# adc_microboard.net
KiCad netlist of a schematic drawn in EAGLE
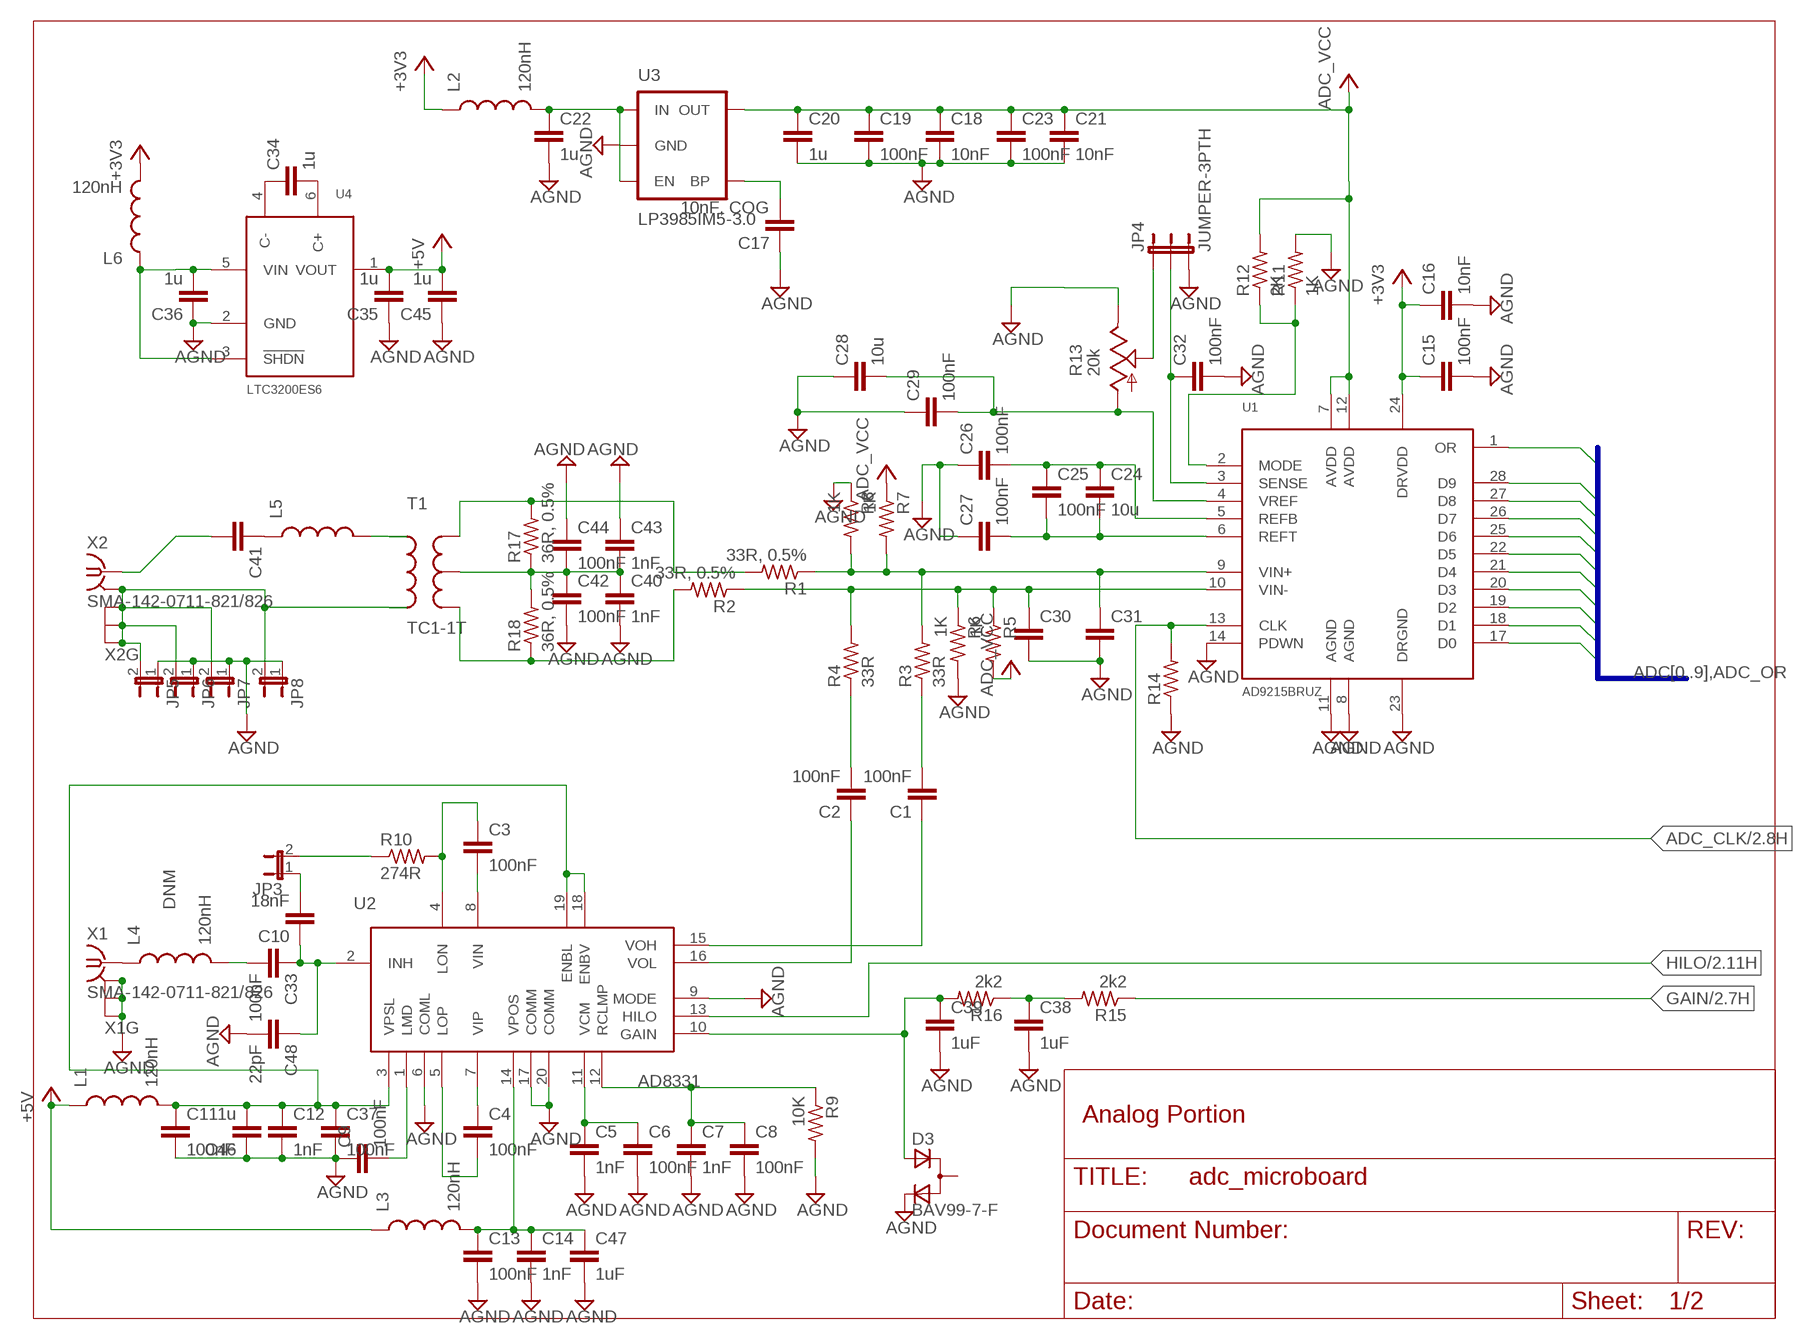
[diagram p0: schematic, sheet 1]
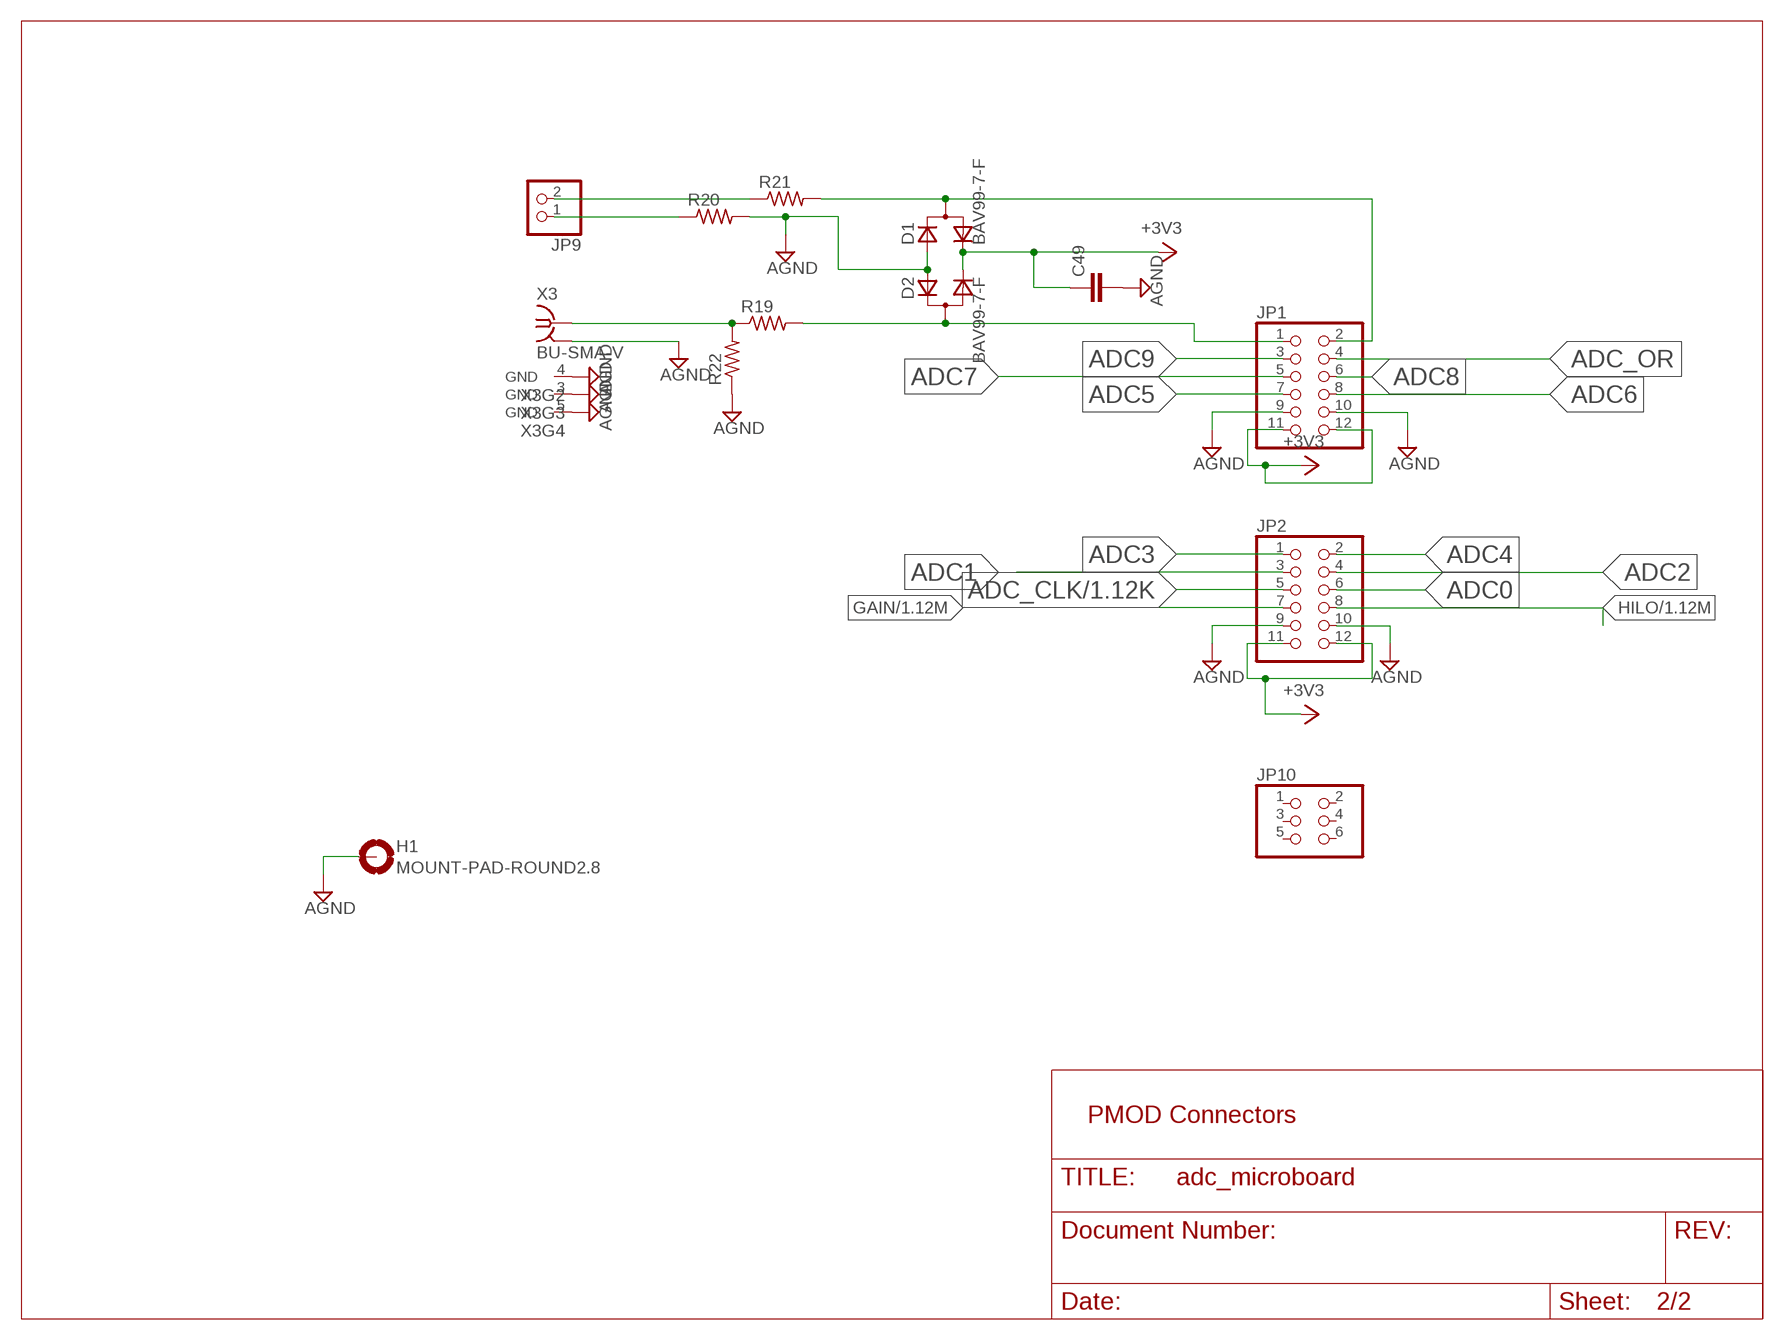
[diagram p1: schematic, sheet 2]

(export (version "E")
  (design (tool "Eeschema 10.0.6"))
  (components
    (comp (ref "C49")
      (value "C-EUC0603")
      (footprint "eagle-import:C0603")
      (libsource (lib "eagle-import") (part "C-EUC0603"))
    )
    (comp (ref "D1")
      (value "BAV99-7-F")
      (footprint "eagle-import:SOT-23")
      (libsource (lib "eagle-import") (part "D_ACACSOT23"))
    )
    (comp (ref "D2")
      (value "BAV99-7-F")
      (footprint "eagle-import:SOT-23")
      (libsource (lib "eagle-import") (part "D_ACACSOT23"))
    )
    (comp (ref "H1")
      (value "MOUNT-PAD-ROUND2.8")
      (footprint "eagle-import:2,8-PAD")
      (libsource (lib "eagle-import") (part "MOUNT-PAD-ROUND2.8"))
    )
    (comp (ref "JP1")
      (value "PINHD-2X6")
      (footprint "eagle-import:2X06")
      (libsource (lib "eagle-import") (part "PINHD-2X6"))
    )
    (comp (ref "JP2")
      (value "PINHD-2X6")
      (footprint "eagle-import:2X06")
      (libsource (lib "eagle-import") (part "PINHD-2X6"))
    )
    (comp (ref "JP9")
      (value "PINHD-1X2/90")
      (footprint "eagle-import:1X02_90")
      (libsource (lib "eagle-import") (part "PINHD-1X2/90"))
    )
    (comp (ref "JP10")
      (value "PINHD-2X3")
      (footprint "eagle-import:2X03")
      (libsource (lib "eagle-import") (part "PINHD-2X3"))
    )
    (comp (ref "R19")
      (value "R-US_R0805")
      (footprint "eagle-import:R0805")
      (libsource (lib "eagle-import") (part "R-US_R0805"))
    )
    (comp (ref "R20")
      (value "R-US_R0603")
      (footprint "eagle-import:R0603")
      (libsource (lib "eagle-import") (part "R-US_R0603"))
    )
    (comp (ref "R21")
      (value "R-US_R0603")
      (footprint "eagle-import:R0603")
      (libsource (lib "eagle-import") (part "R-US_R0603"))
    )
    (comp (ref "R22")
      (value "R-US_R0603")
      (footprint "eagle-import:R0603")
      (libsource (lib "eagle-import") (part "R-US_R0603"))
    )
    (comp (ref "X3")
      (value "BU-SMA-V")
      (footprint "eagle-import:BU-SMA-V")
      (libsource (lib "eagle-import") (part "BU-SMA-V"))
    )
    (comp (ref "C1")
      (value "100nF")
      (footprint "eagle-import:C0603K")
      (libsource (lib "eagle-import") (part "rcl_C-EUC0603K"))
    )
    (comp (ref "C2")
      (value "100nF")
      (footprint "eagle-import:C0603K")
      (libsource (lib "eagle-import") (part "rcl_C-EUC0603K"))
    )
    (comp (ref "C3")
      (value "100nF")
      (footprint "eagle-import:C0402")
      (libsource (lib "eagle-import") (part "rcl_C-EUC0402"))
    )
    (comp (ref "C4")
      (value "100nF")
      (footprint "eagle-import:C0402")
      (libsource (lib "eagle-import") (part "rcl_C-EUC0402"))
    )
    (comp (ref "C5")
      (value "1nF")
      (footprint "eagle-import:C0402")
      (fields (field (name "PART#") "C1005X7R1E102K"))
      (libsource (lib "eagle-import") (part "rcl_C-EUC0402"))
    )
    (comp (ref "C6")
      (value "100nF")
      (footprint "eagle-import:C0402")
      (fields (field (name "PART#") "GRM155R61A104KA01D"))
      (libsource (lib "eagle-import") (part "rcl_C-EUC0402"))
    )
    (comp (ref "C7")
      (value "1nF")
      (footprint "eagle-import:C0402")
      (fields (field (name "PART#") "C1005X7R1E102K"))
      (libsource (lib "eagle-import") (part "rcl_C-EUC0402"))
    )
    (comp (ref "C8")
      (value "100nF")
      (footprint "eagle-import:C0402")
      (fields (field (name "PART#") "GRM155R61A104KA01D"))
      (libsource (lib "eagle-import") (part "rcl_C-EUC0402"))
    )
    (comp (ref "C9")
      (value "100nF")
      (footprint "eagle-import:C0402")
      (fields (field (name "PART#") "GRM155R61A104KA01D"))
      (libsource (lib "eagle-import") (part "rcl_C-EUC0402"))
    )
    (comp (ref "C10")
      (value "18nF")
      (footprint "eagle-import:C0603")
      (libsource (lib "eagle-import") (part "rcl_C-EUC0603"))
    )
    (comp (ref "C11")
      (value "100nF")
      (footprint "eagle-import:C0402")
      (fields (field (name "PART#") "GRM155R61A104KA01D"))
      (libsource (lib "eagle-import") (part "rcl_C-EUC0402"))
    )
    (comp (ref "C12")
      (value "1nF")
      (footprint "eagle-import:C0402")
      (fields (field (name "PART#") "C1005X7R1E102K"))
      (libsource (lib "eagle-import") (part "rcl_C-EUC0402"))
    )
    (comp (ref "C13")
      (value "100nF")
      (footprint "eagle-import:C0402")
      (fields (field (name "PART#") "GRM155R61A104KA01D"))
      (libsource (lib "eagle-import") (part "rcl_C-EUC0402"))
    )
    (comp (ref "C14")
      (value "1nF")
      (footprint "eagle-import:C0402")
      (fields (field (name "PART#") "C1005X7R1E102K"))
      (libsource (lib "eagle-import") (part "rcl_C-EUC0402"))
    )
    (comp (ref "C15")
      (value "100nF")
      (footprint "eagle-import:C0402")
      (fields (field (name "PART#") "GRM155R61A104KA01D"))
      (libsource (lib "eagle-import") (part "rcl_C-EUC0402"))
    )
    (comp (ref "C16")
      (value "10nF")
      (footprint "eagle-import:C0402")
      (libsource (lib "eagle-import") (part "rcl_C-EUC0402"))
    )
    (comp (ref "C17")
      (value "10nF, COG")
      (footprint "eagle-import:C0402")
      (libsource (lib "eagle-import") (part "rcl_C-EUC0402"))
    )
    (comp (ref "C18")
      (value "10nF")
      (footprint "eagle-import:C0402")
      (fields (field (name "PART#") "GRM155R71E103KA01D"))
      (libsource (lib "eagle-import") (part "rcl_C-EUC0402"))
    )
    (comp (ref "C19")
      (value "100nF")
      (footprint "eagle-import:C0402")
      (fields (field (name "PART#") "GRM155R61A104KA01D"))
      (libsource (lib "eagle-import") (part "rcl_C-EUC0402"))
    )
    (comp (ref "C20")
      (value "1u")
      (footprint "eagle-import:C0603")
      (fields (field (name "PART#") "GRM188R61A105KA61D"))
      (libsource (lib "eagle-import") (part "rcl_C-EUC0603"))
    )
    (comp (ref "C21")
      (value "10nF")
      (footprint "eagle-import:C0402")
      (fields (field (name "PART#") "GRM155R71E103KA01D"))
      (libsource (lib "eagle-import") (part "rcl_C-EUC0402"))
    )
    (comp (ref "C22")
      (value "1u")
      (footprint "eagle-import:C0603")
      (fields (field (name "PART#") "GRM188R61A105KA61D"))
      (libsource (lib "eagle-import") (part "rcl_C-EUC0603"))
    )
    (comp (ref "C23")
      (value "100nF")
      (footprint "eagle-import:C0402")
      (fields (field (name "PART#") "GRM155R61A104KA01D"))
      (libsource (lib "eagle-import") (part "rcl_C-EUC0402"))
    )
    (comp (ref "C24")
      (value "10u")
      (footprint "eagle-import:C0603")
      (libsource (lib "eagle-import") (part "rcl_C-EUC0603"))
    )
    (comp (ref "C25")
      (value "100nF")
      (footprint "eagle-import:C0402")
      (fields (field (name "PART#") "GRM155R61A104KA01D"))
      (libsource (lib "eagle-import") (part "rcl_C-EUC0402"))
    )
    (comp (ref "C26")
      (value "100nF")
      (footprint "eagle-import:C0402")
      (fields (field (name "PART#") "GRM155R61A104KA01D"))
      (libsource (lib "eagle-import") (part "rcl_C-EUC0402"))
    )
    (comp (ref "C27")
      (value "100nF")
      (footprint "eagle-import:C0402")
      (fields (field (name "PART#") "GRM155R61A104KA01D"))
      (libsource (lib "eagle-import") (part "rcl_C-EUC0402"))
    )
    (comp (ref "C28")
      (value "10u")
      (footprint "eagle-import:C0603")
      (libsource (lib "eagle-import") (part "rcl_C-EUC0603"))
    )
    (comp (ref "C29")
      (value "100nF")
      (footprint "eagle-import:C0402")
      (fields (field (name "PART#") "GRM155R61A104KA01D"))
      (libsource (lib "eagle-import") (part "rcl_C-EUC0402"))
    )
    (comp (ref "C30")
      (value "C-EUC0402")
      (footprint "eagle-import:C0402")
      (libsource (lib "eagle-import") (part "rcl_C-EUC0402"))
    )
    (comp (ref "C31")
      (value "C-EUC0402")
      (footprint "eagle-import:C0402")
      (libsource (lib "eagle-import") (part "rcl_C-EUC0402"))
    )
    (comp (ref "C32")
      (value "100nF")
      (footprint "eagle-import:C0402")
      (fields (field (name "PART#") "GRM155R61A104KA01D"))
      (libsource (lib "eagle-import") (part "rcl_C-EUC0402"))
    )
    (comp (ref "C33")
      (value "100nF")
      (footprint "eagle-import:C0603K")
      (libsource (lib "eagle-import") (part "rcl_C-EUC0603K"))
    )
    (comp (ref "C34")
      (value "1u")
      (footprint "eagle-import:C0603")
      (fields (field (name "PART#") "GRM188R61A105KA61D"))
      (libsource (lib "eagle-import") (part "rcl_C-EUC0603"))
    )
    (comp (ref "C35")
      (value "1u")
      (footprint "eagle-import:C0603")
      (fields (field (name "PART#") "GRM188R61A105KA61D"))
      (libsource (lib "eagle-import") (part "rcl_C-EUC0603"))
    )
    (comp (ref "C36")
      (value "1u")
      (footprint "eagle-import:C0603")
      (fields (field (name "PART#") "GRM188R61A105KA61D"))
      (libsource (lib "eagle-import") (part "rcl_C-EUC0603"))
    )
    (comp (ref "C37")
      (value "100nF")
      (footprint "eagle-import:C0402")
      (fields (field (name "PART#") "GRM155R61A104KA01D"))
      (libsource (lib "eagle-import") (part "rcl_C-EUC0402"))
    )
    (comp (ref "C38")
      (value "1uF")
      (footprint "eagle-import:C0603")
      (libsource (lib "eagle-import") (part "rcl_C-EUC0603"))
    )
    (comp (ref "C39")
      (value "1uF")
      (footprint "eagle-import:C0603")
      (libsource (lib "eagle-import") (part "rcl_C-EUC0603"))
    )
    (comp (ref "C40")
      (value "1nF")
      (footprint "eagle-import:C0402")
      (fields (field (name "PART#") "C1005X7R1E102K"))
      (libsource (lib "eagle-import") (part "rcl_C-EUC0402"))
    )
    (comp (ref "C41")
      (value "C-EUC0603K")
      (footprint "eagle-import:C0603K")
      (libsource (lib "eagle-import") (part "rcl_C-EUC0603K"))
    )
    (comp (ref "C42")
      (value "100nF")
      (footprint "eagle-import:C0402")
      (fields (field (name "PART#") "GRM155R61A104KA01D"))
      (libsource (lib "eagle-import") (part "rcl_C-EUC0402"))
    )
    (comp (ref "C43")
      (value "1nF")
      (footprint "eagle-import:C0402")
      (fields (field (name "PART#") "C1005X7R1E102K"))
      (libsource (lib "eagle-import") (part "rcl_C-EUC0402"))
    )
    (comp (ref "C44")
      (value "100nF")
      (footprint "eagle-import:C0402")
      (fields (field (name "PART#") "GRM155R61A104KA01D"))
      (libsource (lib "eagle-import") (part "rcl_C-EUC0402"))
    )
    (comp (ref "C45")
      (value "1u")
      (footprint "eagle-import:C0603")
      (fields (field (name "PART#") "GRM188R61A105KA61D"))
      (libsource (lib "eagle-import") (part "rcl_C-EUC0603"))
    )
    (comp (ref "C46")
      (value "1u")
      (footprint "eagle-import:C0402")
      (fields (field (name "PART#") "GRM188R61A105KA61D"))
      (libsource (lib "eagle-import") (part "rcl_C-EUC0402"))
    )
    (comp (ref "C47")
      (value "1uF")
      (footprint "eagle-import:C0402")
      (fields (field (name "PART#") "C1005X7R1E102K"))
      (libsource (lib "eagle-import") (part "rcl_C-EUC0402"))
    )
    (comp (ref "C48")
      (value "22pF")
      (footprint "eagle-import:C0603")
      (libsource (lib "eagle-import") (part "rcl_C-EUC0603"))
    )
    (comp (ref "D3")
      (value "BAV99-7-F")
      (footprint "eagle-import:SOT-23")
      (libsource (lib "eagle-import") (part "D_ACACSOT23"))
    )
    (comp (ref "JP3")
      (value "JUMPER-2SMD-NC")
      (footprint "eagle-import:SJ_2S")
      (libsource (lib "eagle-import") (part "JUMPER-2SMD-NC"))
    )
    (comp (ref "JP4")
      (value "JUMPER-3PTH")
      (footprint "eagle-import:1X03")
      (libsource (lib "eagle-import") (part "JUMPER-3PTH"))
    )
    (comp (ref "JP5")
      (value "JUMPER-2SMD-NC")
      (footprint "eagle-import:SJ_2S")
      (libsource (lib "eagle-import") (part "JUMPER-2SMD-NC"))
    )
    (comp (ref "JP6")
      (value "JUMPER-2SMD-NC")
      (footprint "eagle-import:SJ_2S")
      (libsource (lib "eagle-import") (part "JUMPER-2SMD-NC"))
    )
    (comp (ref "JP7")
      (value "JUMPER-2SMD-NC")
      (footprint "eagle-import:SJ_2S")
      (libsource (lib "eagle-import") (part "JUMPER-2SMD-NC"))
    )
    (comp (ref "JP8")
      (value "JUMPER-2SMD-NC")
      (footprint "eagle-import:SJ_2S")
      (libsource (lib "eagle-import") (part "JUMPER-2SMD-NC"))
    )
    (comp (ref "L1")
      (value "120nH")
      (footprint "eagle-import:0603")
      (fields (field (name "PART#") "MLF1608DR12M"))
      (libsource (lib "eagle-import") (part "INDUCTOR0603"))
    )
    (comp (ref "L2")
      (value "120nH")
      (footprint "eagle-import:0603")
      (libsource (lib "eagle-import") (part "INDUCTOR0603"))
    )
    (comp (ref "L3")
      (value "120nH")
      (footprint "eagle-import:0603")
      (libsource (lib "eagle-import") (part "INDUCTOR0603"))
    )
    (comp (ref "L4")
      (value "120nH")
      (footprint "eagle-import:0603")
      (libsource (lib "eagle-import") (part "INDUCTOR0603"))
    )
    (comp (ref "L5")
      (value "INDUCTOR0603")
      (footprint "eagle-import:0603")
      (libsource (lib "eagle-import") (part "INDUCTOR0603"))
    )
    (comp (ref "L6")
      (value "120nH")
      (footprint "eagle-import:0603")
      (libsource (lib "eagle-import") (part "INDUCTOR0603"))
    )
    (comp (ref "R1")
      (value "33R, 0.5%")
      (footprint "eagle-import:R0603")
      (libsource (lib "eagle-import") (part "R-US_R0603"))
    )
    (comp (ref "R2")
      (value "33R, 0.5%")
      (footprint "eagle-import:R0603")
      (libsource (lib "eagle-import") (part "R-US_R0603"))
    )
    (comp (ref "R3")
      (value "33R")
      (footprint "eagle-import:R0603")
      (libsource (lib "eagle-import") (part "R-US_R0603"))
    )
    (comp (ref "R4")
      (value "33R")
      (footprint "eagle-import:R0603")
      (libsource (lib "eagle-import") (part "R-US_R0603"))
    )
    (comp (ref "R5")
      (value "1K")
      (footprint "eagle-import:R0402")
      (libsource (lib "eagle-import") (part "R-US_R0402"))
    )
    (comp (ref "R6")
      (value "1K")
      (footprint "eagle-import:R0402")
      (libsource (lib "eagle-import") (part "R-US_R0402"))
    )
    (comp (ref "R7")
      (value "1K")
      (footprint "eagle-import:R0402")
      (libsource (lib "eagle-import") (part "R-US_R0402"))
    )
    (comp (ref "R8")
      (value "1K")
      (footprint "eagle-import:R0402")
      (libsource (lib "eagle-import") (part "R-US_R0402"))
    )
    (comp (ref "R9")
      (value "10K")
      (footprint "eagle-import:R0603")
      (libsource (lib "eagle-import") (part "R-US_R0603"))
    )
    (comp (ref "R10")
      (value "274R")
      (footprint "eagle-import:R0603")
      (libsource (lib "eagle-import") (part "R-US_R0603"))
    )
    (comp (ref "R11")
      (value "1K")
      (footprint "eagle-import:R0402")
      (libsource (lib "eagle-import") (part "R-US_R0402"))
    )
    (comp (ref "R12")
      (value "2K")
      (footprint "eagle-import:R0603")
      (libsource (lib "eagle-import") (part "R-US_R0603"))
    )
    (comp (ref "R13")
      (value "20k")
      (footprint "eagle-import:3361P")
      (fields (field (name "PART#") "3361P-1-203GLF"))
      (libsource (lib "eagle-import") (part "TRIM_US-3361P"))
    )
    (comp (ref "R14")
      (value "R-US_R0603")
      (footprint "eagle-import:R0603")
      (libsource (lib "eagle-import") (part "R-US_R0603"))
    )
    (comp (ref "R15")
      (value "2k2")
      (footprint "eagle-import:R0603")
      (libsource (lib "eagle-import") (part "R-US_R0603"))
    )
    (comp (ref "R16")
      (value "2k2")
      (footprint "eagle-import:R0603")
      (libsource (lib "eagle-import") (part "R-US_R0603"))
    )
    (comp (ref "R17")
      (value "36R, 0.5%")
      (footprint "eagle-import:R0603")
      (libsource (lib "eagle-import") (part "R-US_R0603"))
    )
    (comp (ref "R18")
      (value "36R, 0.5%")
      (footprint "eagle-import:R0603")
      (libsource (lib "eagle-import") (part "R-US_R0603"))
    )
    (comp (ref "T1")
      (value "TC1-1T")
      (footprint "eagle-import:AT224-1A")
      (libsource (lib "eagle-import") (part "TC1-1T"))
    )
    (comp (ref "U1")
      (value "AD9215BRUZ")
      (footprint "eagle-import:TSSOP28")
      (libsource (lib "eagle-import") (part "AD9215BRUZ"))
    )
    (comp (ref "U2")
      (value "AD8331")
      (footprint "eagle-import:QSOP20")
      (fields (field (name "PART#") "AD8331ARQZ"))
      (libsource (lib "eagle-import") (part "AD8331"))
    )
    (comp (ref "U3")
      (value "LP3985IM5-3.0")
      (footprint "eagle-import:SOT23-5")
      (libsource (lib "eagle-import") (part "V_REG_LDOSMD"))
    )
    (comp (ref "U4")
      (value "LTC3200ES6")
      (footprint "eagle-import:SOT23-6L")
      (fields (field (name "PART#") "LTC3200ES6-5#TRMPBF"))
      (libsource (lib "eagle-import") (part "LTC3200ES6"))
    )
    (comp (ref "X1")
      (value "SMA-142-0711-821/826")
      (footprint "eagle-import:J502-ND-142-0711-821_826")
      (fields
        (field (name "MF") "JOHNSON COMPONENTS")
        (field (name "MPN") "142-0711-821")
        (field (name "DIGIKEY#") "CONSMA003.062-ND")
      )
      (libsource (lib "eagle-import") (part "SMA-142-0711-821/826"))
    )
    (comp (ref "X2")
      (value "SMA-142-0711-821/826")
      (footprint "eagle-import:J502-ND-142-0711-821_826")
      (fields
        (field (name "MF") "JOHNSON COMPONENTS")
        (field (name "MPN") "142-0711-821")
        (field (name "DIGIKEY#") "CONSMA003.062-ND")
      )
      (libsource (lib "eagle-import") (part "SMA-142-0711-821/826"))
    )
  )
  (nets
    (net (code "1") (name "+3V3") (class "Default")
      (node (ref "C15") (pin "1") (pinfunction "1_1") (pintype "passive"))
      (node (ref "C16") (pin "1") (pinfunction "1_1") (pintype "passive"))
      (node (ref "C49") (pin "1") (pinfunction "1_1") (pintype "passive"))
      (node (ref "D1") (pin "2") (pinfunction "C_2") (pintype "passive"))
      (node (ref "D2") (pin "2") (pinfunction "C_2") (pintype "passive"))
      (node (ref "JP1") (pin "11") (pinfunction "11_11") (pintype "passive"))
      (node (ref "JP1") (pin "12") (pinfunction "12_12") (pintype "passive"))
      (node (ref "JP2") (pin "11") (pinfunction "11_11") (pintype "passive"))
      (node (ref "JP2") (pin "12") (pinfunction "12_12") (pintype "passive"))
      (node (ref "L2") (pin "1") (pinfunction "1_1") (pintype "passive"))
      (node (ref "L6") (pin "2") (pinfunction "2_2") (pintype "passive"))
      (node (ref "U1") (pin "24") (pinfunction "DRVDD_24") (pintype "bidirectional"))
    )
    (net (code "2") (name "+5V") (class "Default")
      (node (ref "C35") (pin "2") (pinfunction "2_2") (pintype "passive"))
      (node (ref "C45") (pin "2") (pinfunction "2_2") (pintype "passive"))
      (node (ref "L1") (pin "1") (pinfunction "1_1") (pintype "passive"))
      (node (ref "L3") (pin "1") (pinfunction "1_1") (pintype "passive"))
      (node (ref "U4") (pin "1") (pinfunction "VOUT_1") (pintype "bidirectional"))
    )
    (net (code "4") (name "ADC0") (class "Default")
      (node (ref "JP2") (pin "6") (pinfunction "6_6") (pintype "passive"))
      (node (ref "U1") (pin "17") (pinfunction "D0_17") (pintype "bidirectional"))
    )
    (net (code "5") (name "ADC1") (class "Default")
      (node (ref "JP2") (pin "3") (pinfunction "3_3") (pintype "passive"))
      (node (ref "U1") (pin "18") (pinfunction "D1_18") (pintype "bidirectional"))
    )
    (net (code "6") (name "ADC2") (class "Default")
      (node (ref "JP2") (pin "4") (pinfunction "4_4") (pintype "passive"))
      (node (ref "U1") (pin "19") (pinfunction "D2_19") (pintype "bidirectional"))
    )
    (net (code "7") (name "ADC3") (class "Default")
      (node (ref "JP2") (pin "1") (pinfunction "1_1") (pintype "passive"))
      (node (ref "U1") (pin "20") (pinfunction "D3_20") (pintype "bidirectional"))
    )
    (net (code "8") (name "ADC4") (class "Default")
      (node (ref "JP2") (pin "2") (pinfunction "2_2") (pintype "passive"))
      (node (ref "U1") (pin "21") (pinfunction "D4_21") (pintype "bidirectional"))
    )
    (net (code "9") (name "ADC5") (class "Default")
      (node (ref "JP1") (pin "7") (pinfunction "7_7") (pintype "passive"))
      (node (ref "U1") (pin "22") (pinfunction "D5_22") (pintype "bidirectional"))
    )
    (net (code "10") (name "ADC6") (class "Default")
      (node (ref "JP1") (pin "8") (pinfunction "8_8") (pintype "passive"))
      (node (ref "U1") (pin "25") (pinfunction "D6_25") (pintype "bidirectional"))
    )
    (net (code "11") (name "ADC7") (class "Default")
      (node (ref "JP1") (pin "5") (pinfunction "5_5") (pintype "passive"))
      (node (ref "U1") (pin "26") (pinfunction "D7_26") (pintype "bidirectional"))
    )
    (net (code "12") (name "ADC8") (class "Default")
      (node (ref "JP1") (pin "6") (pinfunction "6_6") (pintype "passive"))
      (node (ref "U1") (pin "27") (pinfunction "D8_27") (pintype "bidirectional"))
    )
    (net (code "13") (name "ADC9") (class "Default")
      (node (ref "JP1") (pin "3") (pinfunction "3_3") (pintype "passive"))
      (node (ref "U1") (pin "28") (pinfunction "D9_28") (pintype "bidirectional"))
    )
    (net (code "14") (name "ADC_CLK") (class "Default")
      (node (ref "JP2") (pin "5") (pinfunction "5_5") (pintype "passive"))
      (node (ref "R14") (pin "2") (pinfunction "2_2") (pintype "passive"))
      (node (ref "U1") (pin "13") (pinfunction "CLK_13") (pintype "bidirectional"))
    )
    (net (code "15") (name "ADC_OR") (class "Default")
      (node (ref "JP1") (pin "4") (pinfunction "4_4") (pintype "passive"))
      (node (ref "U1") (pin "1") (pinfunction "OR_1") (pintype "bidirectional"))
    )
    (net (code "16") (name "ADC_VCC") (class "Default")
      (node (ref "C18") (pin "1") (pinfunction "1_1") (pintype "passive"))
      (node (ref "C19") (pin "1") (pinfunction "1_1") (pintype "passive"))
      (node (ref "C20") (pin "1") (pinfunction "1_1") (pintype "passive"))
      (node (ref "C21") (pin "1") (pinfunction "1_1") (pintype "passive"))
      (node (ref "C23") (pin "1") (pinfunction "1_1") (pintype "passive"))
      (node (ref "R12") (pin "2") (pinfunction "2_2") (pintype "passive"))
      (node (ref "R5") (pin "2") (pinfunction "2_2") (pintype "passive"))
      (node (ref "R7") (pin "1") (pinfunction "1_1") (pintype "passive"))
      (node (ref "U1") (pin "12") (pinfunction "AVDD_12") (pintype "bidirectional"))
      (node (ref "U1") (pin "7") (pinfunction "AVDD_7") (pintype "bidirectional"))
      (node (ref "U3") (pin "5") (pinfunction "OUT_5") (pintype "passive"))
    )
    (net (code "17") (name "AGND") (class "Default")
      (node (ref "C11") (pin "2") (pinfunction "2_2") (pintype "passive"))
      (node (ref "C12") (pin "2") (pinfunction "2_2") (pintype "passive"))
      (node (ref "C13") (pin "2") (pinfunction "2_2") (pintype "passive"))
      (node (ref "C14") (pin "2") (pinfunction "2_2") (pintype "passive"))
      (node (ref "C15") (pin "2") (pinfunction "2_2") (pintype "passive"))
      (node (ref "C16") (pin "2") (pinfunction "2_2") (pintype "passive"))
      (node (ref "C17") (pin "1") (pinfunction "1_1") (pintype "passive"))
      (node (ref "C18") (pin "2") (pinfunction "2_2") (pintype "passive"))
      (node (ref "C19") (pin "2") (pinfunction "2_2") (pintype "passive"))
      (node (ref "C20") (pin "2") (pinfunction "2_2") (pintype "passive"))
      (node (ref "C21") (pin "2") (pinfunction "2_2") (pintype "passive"))
      (node (ref "C22") (pin "2") (pinfunction "2_2") (pintype "passive"))
      (node (ref "C23") (pin "2") (pinfunction "2_2") (pintype "passive"))
      (node (ref "C26") (pin "1") (pinfunction "1_1") (pintype "passive"))
      (node (ref "C27") (pin "1") (pinfunction "1_1") (pintype "passive"))
      (node (ref "C28") (pin "1") (pinfunction "1_1") (pintype "passive"))
      (node (ref "C29") (pin "1") (pinfunction "1_1") (pintype "passive"))
      (node (ref "C30") (pin "2") (pinfunction "2_2") (pintype "passive"))
      (node (ref "C31") (pin "2") (pinfunction "2_2") (pintype "passive"))
      (node (ref "C32") (pin "2") (pinfunction "2_2") (pintype "passive"))
      (node (ref "C35") (pin "1") (pinfunction "1_1") (pintype "passive"))
      (node (ref "C36") (pin "1") (pinfunction "1_1") (pintype "passive"))
      (node (ref "C37") (pin "2") (pinfunction "2_2") (pintype "passive"))
      (node (ref "C38") (pin "2") (pinfunction "2_2") (pintype "passive"))
      (node (ref "C39") (pin "2") (pinfunction "2_2") (pintype "passive"))
      (node (ref "C40") (pin "2") (pinfunction "2_2") (pintype "passive"))
      (node (ref "C42") (pin "2") (pinfunction "2_2") (pintype "passive"))
      (node (ref "C43") (pin "1") (pinfunction "1_1") (pintype "passive"))
      (node (ref "C44") (pin "1") (pinfunction "1_1") (pintype "passive"))
      (node (ref "C45") (pin "1") (pinfunction "1_1") (pintype "passive"))
      (node (ref "C46") (pin "1") (pinfunction "1_1") (pintype "passive"))
      (node (ref "C47") (pin "2") (pinfunction "2_2") (pintype "passive"))
      (node (ref "C48") (pin "2") (pinfunction "2_2") (pintype "passive"))
      (node (ref "C49") (pin "2") (pinfunction "2_2") (pintype "passive"))
      (node (ref "C5") (pin "2") (pinfunction "2_2") (pintype "passive"))
      (node (ref "C6") (pin "2") (pinfunction "2_2") (pintype "passive"))
      (node (ref "C7") (pin "2") (pinfunction "2_2") (pintype "passive"))
      (node (ref "C8") (pin "2") (pinfunction "2_2") (pintype "passive"))
      (node (ref "C9") (pin "1") (pinfunction "1_1") (pintype "passive"))
      (node (ref "D1") (pin "3") (pinfunction "A_3") (pintype "passive"))
      (node (ref "D2") (pin "3") (pinfunction "A_3") (pintype "passive"))
      (node (ref "D3") (pin "2") (pinfunction "C_2") (pintype "passive"))
      (node (ref "H1") (pin "B2,8") (pinfunction "MOUNT_B2,8") (pintype "passive"))
      (node (ref "JP1") (pin "10") (pinfunction "10_10") (pintype "passive"))
      (node (ref "JP1") (pin "9") (pinfunction "9_9") (pintype "passive"))
      (node (ref "JP2") (pin "10") (pinfunction "10_10") (pintype "passive"))
      (node (ref "JP2") (pin "9") (pinfunction "9_9") (pintype "passive"))
      (node (ref "JP4") (pin "3") (pinfunction "3_3") (pintype "passive"))
      (node (ref "JP5") (pin "1") (pinfunction "1_1") (pintype "passive"))
      (node (ref "JP6") (pin "1") (pinfunction "1_1") (pintype "passive"))
      (node (ref "JP7") (pin "1") (pinfunction "1_1") (pintype "passive"))
      (node (ref "JP8") (pin "1") (pinfunction "1_1") (pintype "passive"))
      (node (ref "R11") (pin "2") (pinfunction "2_2") (pintype "passive"))
      (node (ref "R13") (pin "1") (pinfunction "E_1") (pintype "passive"))
      (node (ref "R14") (pin "1") (pinfunction "1_1") (pintype "passive"))
      (node (ref "R20") (pin "2") (pinfunction "2_2") (pintype "passive"))
      (node (ref "R22") (pin "1") (pinfunction "1_1") (pintype "passive"))
      (node (ref "R6") (pin "2") (pinfunction "2_2") (pintype "passive"))
      (node (ref "R8") (pin "1") (pinfunction "1_1") (pintype "passive"))
      (node (ref "R9") (pin "2") (pinfunction "2_2") (pintype "passive"))
      (node (ref "U1") (pin "11") (pinfunction "AGND_11") (pintype "bidirectional"))
      (node (ref "U1") (pin "14") (pinfunction "PDWN_14") (pintype "bidirectional"))
      (node (ref "U1") (pin "23") (pinfunction "DRGND_23") (pintype "bidirectional"))
      (node (ref "U1") (pin "8") (pinfunction "AGND_8") (pintype "bidirectional"))
      (node (ref "U2") (pin "17") (pinfunction "COMM_17") (pintype "bidirectional"))
      (node (ref "U2") (pin "20") (pinfunction "COMM_20") (pintype "bidirectional"))
      (node (ref "U2") (pin "6") (pinfunction "COML_6") (pintype "bidirectional"))
      (node (ref "U2") (pin "9") (pinfunction "MODE_9") (pintype "bidirectional"))
      (node (ref "U3") (pin "2") (pinfunction "GND_2") (pintype "input"))
      (node (ref "U4") (pin "2") (pinfunction "GND_2") (pintype "bidirectional"))
      (node (ref "X1") (pin "G@1") (pinfunction "GND_G@1") (pintype "power_in"))
      (node (ref "X1") (pin "G@2") (pinfunction "GND_G@2") (pintype "power_in"))
      (node (ref "X1") (pin "G@3") (pinfunction "GND_G@3") (pintype "power_in"))
      (node (ref "X1") (pin "G@4") (pinfunction "GND_G@4") (pintype "power_in"))
      (node (ref "X3") (pin "2") (pinfunction "GND_2") (pintype "power_in"))
      (node (ref "X3") (pin "3") (pinfunction "GND_3") (pintype "power_in"))
      (node (ref "X3") (pin "4") (pinfunction "GND_4") (pintype "power_in"))
      (node (ref "X3") (pin "5") (pinfunction "GND_5") (pintype "power_in"))
    )
    (net (code "18") (name "GAIN") (class "Default")
      (node (ref "JP2") (pin "7") (pinfunction "7_7") (pintype "passive"))
      (node (ref "R15") (pin "1") (pinfunction "1_1") (pintype "passive"))
    )
    (net (code "19") (name "HILO") (class "Default")
      (node (ref "JP2") (pin "8") (pinfunction "8_8") (pintype "passive"))
      (node (ref "U2") (pin "13") (pinfunction "HILO_13") (pintype "bidirectional"))
    )
    (net (code "20") (name "Net-(C1-Pad2)") (class "Default")
      (node (ref "C1") (pin "2") (pinfunction "2_2") (pintype "passive"))
      (node (ref "R3") (pin "1") (pinfunction "1_1") (pintype "passive"))
    )
    (net (code "21") (name "Net-(C2-Pad2)") (class "Default")
      (node (ref "C2") (pin "2") (pinfunction "2_2") (pintype "passive"))
      (node (ref "R4") (pin "1") (pinfunction "1_1") (pintype "passive"))
    )
    (net (code "22") (name "Net-(C10-Pad2)") (class "Default")
      (node (ref "C10") (pin "2") (pinfunction "2_2") (pintype "passive"))
      (node (ref "JP3") (pin "1") (pinfunction "1_1") (pintype "passive"))
    )
    (net (code "23") (name "Net-(C33-Pad2)") (class "Default")
      (node (ref "C33") (pin "2") (pinfunction "2_2") (pintype "passive"))
      (node (ref "L4") (pin "2") (pinfunction "2_2") (pintype "passive"))
    )
    (net (code "24") (name "Net-(C38-Pad1)") (class "Default")
      (node (ref "C38") (pin "1") (pinfunction "1_1") (pintype "passive"))
      (node (ref "R15") (pin "2") (pinfunction "2_2") (pintype "passive"))
      (node (ref "R16") (pin "1") (pinfunction "1_1") (pintype "passive"))
    )
    (net (code "25") (name "Net-(C41-Pad1)") (class "Default")
      (node (ref "C41") (pin "1") (pinfunction "1_1") (pintype "passive"))
      (node (ref "L5") (pin "1") (pinfunction "1_1") (pintype "passive"))
    )
    (net (code "26") (name "Net-(C41-Pad2)") (class "Default")
      (node (ref "C41") (pin "2") (pinfunction "2_2") (pintype "passive"))
      (node (ref "X2") (pin "1") (pinfunction "1_1") (pintype "passive"))
    )
    (net (code "27") (name "Net-(D1-CA)") (class "Default")
      (node (ref "D1") (pin "1") (pinfunction "CA_1") (pintype "passive"))
      (node (ref "JP1") (pin "2") (pinfunction "2_2") (pintype "passive"))
      (node (ref "R21") (pin "2") (pinfunction "2_2") (pintype "passive"))
    )
    (net (code "28") (name "Net-(D2-CA)") (class "Default")
      (node (ref "D2") (pin "1") (pinfunction "CA_1") (pintype "passive"))
      (node (ref "JP1") (pin "1") (pinfunction "1_1") (pintype "passive"))
      (node (ref "R19") (pin "2") (pinfunction "2_2") (pintype "passive"))
    )
    (net (code "29") (name "Net-(D3-A)") (class "Default")
      (node (ref "C39") (pin "1") (pinfunction "1_1") (pintype "passive"))
      (node (ref "D3") (pin "3") (pinfunction "A_3") (pintype "passive"))
      (node (ref "R16") (pin "2") (pinfunction "2_2") (pintype "passive"))
      (node (ref "U2") (pin "10") (pinfunction "GAIN_10") (pintype "bidirectional"))
    )
    (net (code "30") (name "Net-(JP3-Pad2)") (class "Default")
      (node (ref "JP3") (pin "2") (pinfunction "2_2") (pintype "passive"))
      (node (ref "R10") (pin "1") (pinfunction "1_1") (pintype "passive"))
    )
    (net (code "31") (name "Net-(JP9-Pad1)") (class "Default")
      (node (ref "JP9") (pin "1") (pinfunction "1_1") (pintype "passive"))
      (node (ref "R20") (pin "1") (pinfunction "1_1") (pintype "passive"))
    )
    (net (code "32") (name "Net-(JP9-Pad2)") (class "Default")
      (node (ref "JP9") (pin "2") (pinfunction "2_2") (pintype "passive"))
      (node (ref "R21") (pin "1") (pinfunction "1_1") (pintype "passive"))
    )
    (net (code "33") (name "Net-(L4-Pad1)") (class "Default")
      (node (ref "L4") (pin "1") (pinfunction "1_1") (pintype "passive"))
      (node (ref "X1") (pin "1") (pinfunction "1_1") (pintype "passive"))
    )
    (net (code "34") (name "Net-(R13-A)") (class "Default")
      (node (ref "C28") (pin "2") (pinfunction "2_2") (pintype "passive"))
      (node (ref "C29") (pin "2") (pinfunction "2_2") (pintype "passive"))
      (node (ref "R13") (pin "3") (pinfunction "A_3") (pintype "passive"))
      (node (ref "U1") (pin "4") (pinfunction "VREF_4") (pintype "bidirectional"))
    )
    (net (code "35") (name "Net-(R13-S)") (class "Default")
      (node (ref "JP4") (pin "1") (pinfunction "1_1") (pintype "passive"))
      (node (ref "R13") (pin "2") (pinfunction "S_2") (pintype "passive"))
    )
    (net (code "36") (name "Net-(R19-Pad1)") (class "Default")
      (node (ref "R19") (pin "1") (pinfunction "1_1") (pintype "passive"))
      (node (ref "R22") (pin "2") (pinfunction "2_2") (pintype "passive"))
      (node (ref "X3") (pin "1") (pinfunction "1_1") (pintype "passive"))
    )
    (net (code "37") (name "Net-(T1-P1)") (class "Default")
      (node (ref "L5") (pin "2") (pinfunction "2_2") (pintype "passive"))
      (node (ref "T1") (pin "6") (pinfunction "P1_6") (pintype "passive"))
    )
    (net (code "38") (name "Net-(T1-P2)") (class "Default")
      (node (ref "JP5") (pin "2") (pinfunction "2_2") (pintype "passive"))
      (node (ref "JP6") (pin "2") (pinfunction "2_2") (pintype "passive"))
      (node (ref "JP7") (pin "2") (pinfunction "2_2") (pintype "passive"))
      (node (ref "JP8") (pin "2") (pinfunction "2_2") (pintype "passive"))
      (node (ref "T1") (pin "4") (pinfunction "P2_4") (pintype "passive"))
      (node (ref "X2") (pin "G@1") (pinfunction "GND_G@1") (pintype "power_in"))
      (node (ref "X2") (pin "G@2") (pinfunction "GND_G@2") (pintype "power_in"))
      (node (ref "X2") (pin "G@3") (pinfunction "GND_G@3") (pintype "power_in"))
      (node (ref "X2") (pin "G@4") (pinfunction "GND_G@4") (pintype "power_in"))
    )
    (net (code "39") (name "Net-(T1-S1)") (class "Default")
      (node (ref "R1") (pin "2") (pinfunction "2_2") (pintype "passive"))
      (node (ref "R17") (pin "2") (pinfunction "2_2") (pintype "passive"))
      (node (ref "T1") (pin "1") (pinfunction "S1_1") (pintype "passive"))
    )
    (net (code "40") (name "Net-(T1-S2)") (class "Default")
      (node (ref "R18") (pin "1") (pinfunction "1_1") (pintype "passive"))
      (node (ref "R2") (pin "2") (pinfunction "2_2") (pintype "passive"))
      (node (ref "T1") (pin "3") (pinfunction "S2_3") (pintype "passive"))
    )
    (net (code "41") (name "Net-(T1-ST)") (class "Default")
      (node (ref "C40") (pin "1") (pinfunction "1_1") (pintype "passive"))
      (node (ref "C42") (pin "1") (pinfunction "1_1") (pintype "passive"))
      (node (ref "C43") (pin "2") (pinfunction "2_2") (pintype "passive"))
      (node (ref "C44") (pin "2") (pinfunction "2_2") (pintype "passive"))
      (node (ref "R17") (pin "1") (pinfunction "1_1") (pintype "passive"))
      (node (ref "R18") (pin "2") (pinfunction "2_2") (pintype "passive"))
      (node (ref "T1") (pin "2") (pinfunction "ST_2") (pintype "passive"))
    )
    (net (code "42") (name "Net-(U1-MODE)") (class "Default")
      (node (ref "R11") (pin "1") (pinfunction "1_1") (pintype "passive"))
      (node (ref "R12") (pin "1") (pinfunction "1_1") (pintype "passive"))
      (node (ref "U1") (pin "2") (pinfunction "MODE_2") (pintype "bidirectional"))
    )
    (net (code "43") (name "Net-(U1-REFB)") (class "Default")
      (node (ref "C24") (pin "1") (pinfunction "1_1") (pintype "passive"))
      (node (ref "C25") (pin "1") (pinfunction "1_1") (pintype "passive"))
      (node (ref "C26") (pin "2") (pinfunction "2_2") (pintype "passive"))
      (node (ref "U1") (pin "5") (pinfunction "REFB_5") (pintype "bidirectional"))
    )
    (net (code "44") (name "Net-(U1-REFT)") (class "Default")
      (node (ref "C24") (pin "2") (pinfunction "2_2") (pintype "passive"))
      (node (ref "C25") (pin "2") (pinfunction "2_2") (pintype "passive"))
      (node (ref "C27") (pin "2") (pinfunction "2_2") (pintype "passive"))
      (node (ref "U1") (pin "6") (pinfunction "REFT_6") (pintype "bidirectional"))
    )
    (net (code "45") (name "Net-(U1-SENSE)") (class "Default")
      (node (ref "C32") (pin "1") (pinfunction "1_1") (pintype "passive"))
      (node (ref "JP4") (pin "2") (pinfunction "2_2") (pintype "passive"))
      (node (ref "U1") (pin "3") (pinfunction "SENSE_3") (pintype "bidirectional"))
    )
    (net (code "46") (name "Net-(U1-VIN+)") (class "Default")
      (node (ref "C31") (pin "1") (pinfunction "1_1") (pintype "passive"))
      (node (ref "R1") (pin "1") (pinfunction "1_1") (pintype "passive"))
      (node (ref "R3") (pin "2") (pinfunction "2_2") (pintype "passive"))
      (node (ref "R7") (pin "2") (pinfunction "2_2") (pintype "passive"))
      (node (ref "R8") (pin "2") (pinfunction "2_2") (pintype "passive"))
      (node (ref "U1") (pin "9") (pinfunction "VIN+_9") (pintype "bidirectional"))
    )
    (net (code "47") (name "Net-(U1-VIN-)") (class "Default")
      (node (ref "C30") (pin "1") (pinfunction "1_1") (pintype "passive"))
      (node (ref "R2") (pin "1") (pinfunction "1_1") (pintype "passive"))
      (node (ref "R4") (pin "2") (pinfunction "2_2") (pintype "passive"))
      (node (ref "R5") (pin "1") (pinfunction "1_1") (pintype "passive"))
      (node (ref "R6") (pin "1") (pinfunction "1_1") (pintype "passive"))
      (node (ref "U1") (pin "10") (pinfunction "VIN-_10") (pintype "bidirectional"))
    )
    (net (code "48") (name "Net-(U2-ENBL)") (class "Default")
      (node (ref "C11") (pin "1") (pinfunction "1_1") (pintype "passive"))
      (node (ref "C12") (pin "1") (pinfunction "1_1") (pintype "passive"))
      (node (ref "C37") (pin "1") (pinfunction "1_1") (pintype "passive"))
      (node (ref "C46") (pin "2") (pinfunction "2_2") (pintype "passive"))
      (node (ref "L1") (pin "2") (pinfunction "2_2") (pintype "passive"))
      (node (ref "U2") (pin "18") (pinfunction "ENBV_18") (pintype "bidirectional"))
      (node (ref "U2") (pin "19") (pinfunction "ENBL_19") (pintype "bidirectional"))
      (node (ref "U2") (pin "3") (pinfunction "VPSL_3") (pintype "bidirectional"))
    )
    (net (code "49") (name "Net-(U2-INH)") (class "Default")
      (node (ref "C10") (pin "1") (pinfunction "1_1") (pintype "passive"))
      (node (ref "C33") (pin "1") (pinfunction "1_1") (pintype "passive"))
      (node (ref "C48") (pin "1") (pinfunction "1_1") (pintype "passive"))
      (node (ref "U2") (pin "2") (pinfunction "INH_2") (pintype "bidirectional"))
    )
    (net (code "50") (name "Net-(U2-LMD)") (class "Default")
      (node (ref "C9") (pin "2") (pinfunction "2_2") (pintype "passive"))
      (node (ref "U2") (pin "1") (pinfunction "LMD_1") (pintype "bidirectional"))
    )
    (net (code "51") (name "Net-(U2-LON)") (class "Default")
      (node (ref "C3") (pin "1") (pinfunction "1_1") (pintype "passive"))
      (node (ref "R10") (pin "2") (pinfunction "2_2") (pintype "passive"))
      (node (ref "U2") (pin "4") (pinfunction "LON_4") (pintype "bidirectional"))
    )
    (net (code "52") (name "Net-(U2-LOP)") (class "Default")
      (node (ref "C4") (pin "2") (pinfunction "2_2") (pintype "passive"))
      (node (ref "U2") (pin "5") (pinfunction "LOP_5") (pintype "bidirectional"))
    )
    (net (code "53") (name "Net-(U2-RCLMP)") (class "Default")
      (node (ref "C7") (pin "1") (pinfunction "1_1") (pintype "passive"))
      (node (ref "C8") (pin "1") (pinfunction "1_1") (pintype "passive"))
      (node (ref "R9") (pin "1") (pinfunction "1_1") (pintype "passive"))
      (node (ref "U2") (pin "12") (pinfunction "RCLMP_12") (pintype "bidirectional"))
    )
    (net (code "54") (name "Net-(U2-VCM)") (class "Default")
      (node (ref "C5") (pin "1") (pinfunction "1_1") (pintype "passive"))
      (node (ref "C6") (pin "1") (pinfunction "1_1") (pintype "passive"))
      (node (ref "U2") (pin "11") (pinfunction "VCM_11") (pintype "bidirectional"))
    )
    (net (code "55") (name "Net-(U2-VIN)") (class "Default")
      (node (ref "C3") (pin "2") (pinfunction "2_2") (pintype "passive"))
      (node (ref "U2") (pin "8") (pinfunction "VIN_8") (pintype "bidirectional"))
    )
    (net (code "56") (name "Net-(U2-VIP)") (class "Default")
      (node (ref "C4") (pin "1") (pinfunction "1_1") (pintype "passive"))
      (node (ref "U2") (pin "7") (pinfunction "VIP_7") (pintype "bidirectional"))
    )
    (net (code "57") (name "Net-(U2-VOH)") (class "Default")
      (node (ref "C1") (pin "1") (pinfunction "1_1") (pintype "passive"))
      (node (ref "U2") (pin "15") (pinfunction "VOH_15") (pintype "bidirectional"))
    )
    (net (code "58") (name "Net-(U2-VOL)") (class "Default")
      (node (ref "C2") (pin "1") (pinfunction "1_1") (pintype "passive"))
      (node (ref "U2") (pin "16") (pinfunction "VOL_16") (pintype "bidirectional"))
    )
    (net (code "59") (name "Net-(U2-VPOS)") (class "Default")
      (node (ref "C13") (pin "1") (pinfunction "1_1") (pintype "passive"))
      (node (ref "C14") (pin "1") (pinfunction "1_1") (pintype "passive"))
      (node (ref "C47") (pin "1") (pinfunction "1_1") (pintype "passive"))
      (node (ref "L3") (pin "2") (pinfunction "2_2") (pintype "passive"))
      (node (ref "U2") (pin "14") (pinfunction "VPOS_14") (pintype "bidirectional"))
    )
    (net (code "60") (name "Net-(U3-BP)") (class "Default")
      (node (ref "C17") (pin "2") (pinfunction "2_2") (pintype "passive"))
      (node (ref "U3") (pin "4") (pinfunction "BP_4") (pintype "input"))
    )
    (net (code "61") (name "Net-(U3-EN)") (class "Default")
      (node (ref "C22") (pin "1") (pinfunction "1_1") (pintype "passive"))
      (node (ref "L2") (pin "2") (pinfunction "2_2") (pintype "passive"))
      (node (ref "U3") (pin "1") (pinfunction "IN_1") (pintype "input"))
      (node (ref "U3") (pin "3") (pinfunction "EN_3") (pintype "input"))
    )
    (net (code "62") (name "Net-(U4-C+)") (class "Default")
      (node (ref "C34") (pin "2") (pinfunction "2_2") (pintype "passive"))
      (node (ref "U4") (pin "6") (pinfunction "C+_6") (pintype "bidirectional"))
    )
    (net (code "63") (name "Net-(U4-C-)") (class "Default")
      (node (ref "C34") (pin "1") (pinfunction "1_1") (pintype "passive"))
      (node (ref "U4") (pin "4") (pinfunction "C-_4") (pintype "bidirectional"))
    )
    (net (code "64") (name "Net-(U4-VIN)") (class "Default")
      (node (ref "C36") (pin "2") (pinfunction "2_2") (pintype "passive"))
      (node (ref "L6") (pin "1") (pinfunction "1_1") (pintype "passive"))
      (node (ref "U4") (pin "3") (pinfunction "~{SHDN}_3") (pintype "bidirectional"))
      (node (ref "U4") (pin "5") (pinfunction "VIN_5") (pintype "bidirectional"))
    )
    (net (code "65") (name "unconnected-(D3-CA-Pad1)") (class "Default")
      (node (ref "D3") (pin "1") (pinfunction "CA_1") (pintype "passive"))
    )
    (net (code "66") (name "unconnected-(JP10-Pad1)") (class "Default")
      (node (ref "JP10") (pin "1") (pinfunction "1_1") (pintype "passive"))
    )
    (net (code "67") (name "unconnected-(JP10-Pad2)") (class "Default")
      (node (ref "JP10") (pin "2") (pinfunction "2_2") (pintype "passive"))
    )
    (net (code "68") (name "unconnected-(JP10-Pad3)") (class "Default")
      (node (ref "JP10") (pin "3") (pinfunction "3_3") (pintype "passive"))
    )
    (net (code "69") (name "unconnected-(JP10-Pad4)") (class "Default")
      (node (ref "JP10") (pin "4") (pinfunction "4_4") (pintype "passive"))
    )
    (net (code "70") (name "unconnected-(JP10-Pad5)") (class "Default")
      (node (ref "JP10") (pin "5") (pinfunction "5_5") (pintype "passive"))
    )
    (net (code "71") (name "unconnected-(JP10-Pad6)") (class "Default")
      (node (ref "JP10") (pin "6") (pinfunction "6_6") (pintype "passive"))
    )
  )
)
